# Power.net
KiCad netlist of a schematic drawn in Altium Designer
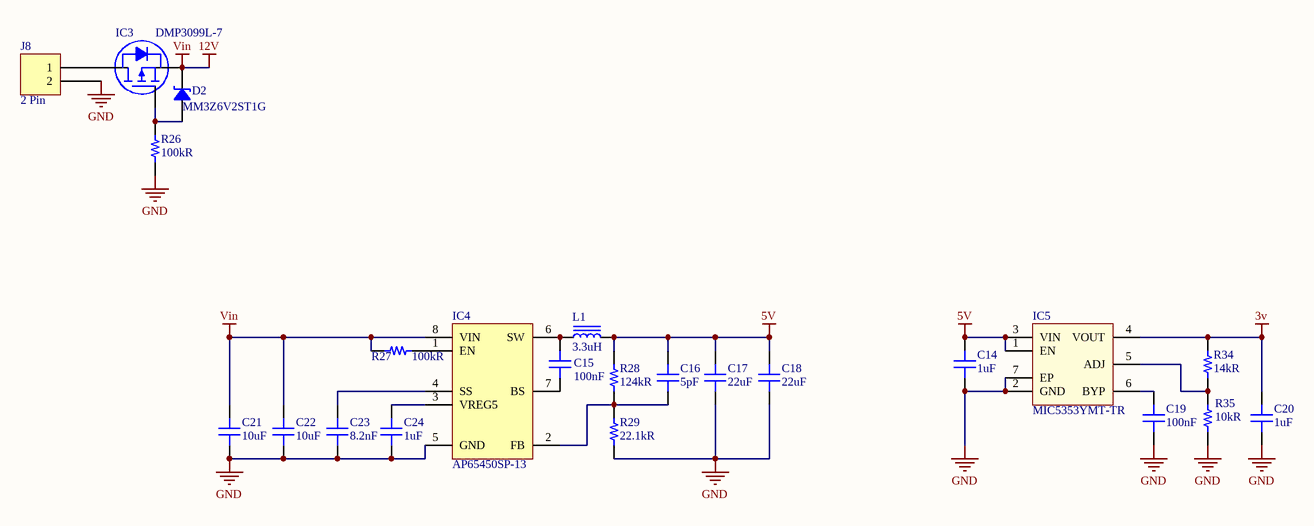
[diagram p0: Power.SchDoc]

(export (version "E")
  (design (tool "Eeschema 10.0.6"))
  (components
    (comp (ref "C14")
      (value "1uF")
      (footprint "CAP 0603/1608")
      (description "Ceramic, SMT Capacitor")
      (fields
        (field (name "MANUFACTURER") "Samsung")
        (field (name "MANUFACTURER PART NUMBER") "CL10A105KP8NNNC")
      )
      (libsource (lib "yildizIoT Library") (part "Capacitor - Ceramic"))
    )
    (comp (ref "C15")
      (value "100nF")
      (footprint "CAP 0603/1608")
      (description "Ceramic, SMT Capacitor")
      (fields
        (field (name "MANUFACTURER") "Samsung")
        (field (name "MANUFACTURER PART NUMBER") "CL10B104JB8NNNC")
      )
      (libsource (lib "yildizIoT Library") (part "Capacitor - Ceramic"))
    )
    (comp (ref "C16")
      (value "5pF")
      (footprint "CAP 0603/1608")
      (description "Ceramic, SMT Capacitor")
      (fields
        (field (name "MANUFACTURER") "Samsung")
        (field (name "MANUFACTURER PART NUMBER") "CL10C050BB8NNNC")
      )
      (libsource (lib "yildizIoT Library") (part "Capacitor - Ceramic"))
    )
    (comp (ref "C17")
      (value "22uF")
      (footprint "CAP 0603/1608")
      (description "Ceramic, SMT Capacitor")
      (fields
        (field (name "MANUFACTURER") "Samsung")
        (field (name "MANUFACTURER PART NUMBER") "CL10A226MPCNUBE")
      )
      (libsource (lib "yildizIoT Library") (part "Capacitor - Ceramic"))
    )
    (comp (ref "C18")
      (value "22uF")
      (footprint "CAP 0603/1608")
      (description "Ceramic, SMT Capacitor")
      (fields
        (field (name "MANUFACTURER") "Samsung")
        (field (name "MANUFACTURER PART NUMBER") "CL10A226MPCNUBE")
      )
      (libsource (lib "yildizIoT Library") (part "Capacitor - Ceramic"))
    )
    (comp (ref "C19")
      (value "100nF")
      (footprint "CAP 0603/1608")
      (description "Ceramic, SMT Capacitor")
      (fields
        (field (name "MANUFACTURER") "Samsung")
        (field (name "MANUFACTURER PART NUMBER") "CL10B104JB8NNNC")
      )
      (libsource (lib "yildizIoT Library") (part "Capacitor - Ceramic"))
    )
    (comp (ref "C20")
      (value "1uF")
      (footprint "CAP 0603/1608")
      (description "Ceramic, SMT Capacitor")
      (fields
        (field (name "MANUFACTURER") "Samsung")
        (field (name "MANUFACTURER PART NUMBER") "CL10A105KP8NNNC")
      )
      (libsource (lib "yildizIoT Library") (part "Capacitor - Ceramic"))
    )
    (comp (ref "C21")
      (value "10uF")
      (footprint "CAP 0603/1608")
      (description "Ceramic, SMT Capacitor")
      (fields
        (field (name "MANUFACTURER") "Samsung")
        (field (name "MANUFACTURER PART NUMBER") "CL10A106MQ8NNNC")
      )
      (libsource (lib "yildizIoT Library") (part "Capacitor - Ceramic"))
    )
    (comp (ref "C22")
      (value "10uF")
      (footprint "CAP 0603/1608")
      (description "Ceramic, SMT Capacitor")
      (fields
        (field (name "MANUFACTURER") "Samsung")
        (field (name "MANUFACTURER PART NUMBER") "CL10A106MQ8NNNC")
      )
      (libsource (lib "yildizIoT Library") (part "Capacitor - Ceramic"))
    )
    (comp (ref "C23")
      (value "8.2nF")
      (footprint "CAP 0603/1608")
      (description "Ceramic, SMT Capacitor")
      (fields
        (field (name "MANUFACTURER") "Walsin Technologies")
        (field (name "MANUFACTURER PART NUMBER") "0603B822K500CT")
      )
      (libsource (lib "yildizIoT Library") (part "Capacitor - Ceramic"))
    )
    (comp (ref "C24")
      (value "1uF")
      (footprint "CAP 0603/1608")
      (description "Ceramic, SMT Capacitor")
      (fields
        (field (name "MANUFACTURER") "Samsung")
        (field (name "MANUFACTURER PART NUMBER") "CL10A105KP8NNNC")
      )
      (libsource (lib "yildizIoT Library") (part "Capacitor - Ceramic"))
    )
    (comp (ref "D2")
      (value "MM3Z6V2ST1G")
      (footprint "SOD323")
      (description "DIODE ZENER 6.2V 300MW SOD323")
      (fields (field (name "MANUFACTURER") "ON Semiconductor") (field (name "TOLERANCE") "2%"))
      (libsource (lib "Celestial Altium Library - altium_library") (part "Diode Zener"))
    )
    (comp (ref "IC3")
      (value "DMP3099L-7")
      (footprint "DIODES SOT-23-3")
      (description "MOSFET P-CH 30V SOT23")
      (fields (field (name "MANUFACTURER") "Diodes"))
      (libsource (lib "Celestial Altium Library - altium_library") (part "DIODES MOSFET P-CH SOT-23-3"))
    )
    (comp (ref "IC4")
      (value "AP65450SP-13")
      (footprint "DIODES SO-8EP")
      (fields (field (name "MANUFACTURER") "Diodes"))
      (libsource (lib "yildizIoT Library") (part "DIODES AP65450"))
    )
    (comp (ref "IC5")
      (value "MIC5353YMT-TR")
      (footprint "MICREL MLF-6 1.6x1.6MM")
      (description "Integrated Circuit")
      (fields (field (name "MANUFACTURER") "Microchip"))
      (libsource (lib "yildizIoT Library") (part "MICROCHIP MIC5353"))
    )
    (comp (ref "J8")
      (value "2 Pin")
      (footprint "TE 282834-2")
      (libsource (lib "yildizIoT Library") (part "2 Pin"))
    )
    (comp (ref "L1")
      (value "3.3uH")
      (footprint "MURATA 1264EY-4R7M=P3")
      (fields
        (field (name "MANUFACTURER") "Murata")
        (field (name "MANUFACTURER PART NUMBER") "1264EY-3R3N=P3")
        (field (name "TOLERANCE") "30%")
      )
      (libsource (lib "yildizIoT Library") (part "Inductor Iron Core"))
    )
    (comp (ref "R26")
      (value "100kR")
      (footprint "RES 0603/1608")
      (description "Ceramic, SMT Capacitor")
      (fields
        (field (name "MANUFACTURER") "Susumu")
        (field (name "MANUFACTURER PART NUMBER") "RR0816P-104-D")
      )
      (libsource (lib "yildizIoT Library") (part "Resistor_Chip"))
    )
    (comp (ref "R27")
      (value "100kR")
      (footprint "RES 0603/1608")
      (description "Ceramic, SMT Capacitor")
      (fields
        (field (name "MANUFACTURER") "Susumu")
        (field (name "MANUFACTURER PART NUMBER") "RR0816P-104-D")
      )
      (libsource (lib "yildizIoT Library") (part "Resistor_Chip"))
    )
    (comp (ref "R28")
      (value "124kR")
      (footprint "RES 0603/1608")
      (description "Ceramic, SMT Capacitor")
      (fields
        (field (name "MANUFACTURER") "Stackpole Electronics")
        (field (name "MANUFACTURER PART NUMBER") "RMCF0603FT124K")
      )
      (libsource (lib "yildizIoT Library") (part "Resistor_Chip"))
    )
    (comp (ref "R29")
      (value "22.1kR")
      (footprint "RES 0603/1608")
      (description "Ceramic, SMT Capacitor")
      (fields
        (field (name "MANUFACTURER") "Stackpole Electronics")
        (field (name "MANUFACTURER PART NUMBER") "RMCF0603FT22K1")
      )
      (libsource (lib "yildizIoT Library") (part "Resistor_Chip"))
    )
    (comp (ref "R34")
      (value "14kR")
      (footprint "RES 0603/1608")
      (description "Ceramic, SMT Capacitor")
      (fields
        (field (name "MANUFACTURER") "Yageo")
        (field (name "MANUFACTURER PART NUMBER") "RC0603FR-0714KL")
      )
      (libsource (lib "yildizIoT Library") (part "Resistor_Chip"))
    )
    (comp (ref "R35")
      (value "10kR")
      (footprint "RES 0603/1608")
      (description "Ceramic, SMT Capacitor")
      (fields
        (field (name "MANUFACTURER") "Stackpole Electronics")
        (field (name "MANUFACTURER PART NUMBER") "RNCP0603FTD10K0")
      )
      (libsource (lib "yildizIoT Library") (part "Resistor_Chip"))
    )
  )
  (nets
    (net (code "1") (name "3v") (class "Default")
      (node (ref "C20") (pin "2") (pinfunction "2_2") (pintype "passive"))
      (node (ref "IC5") (pin "4") (pinfunction "VOUT_4") (pintype "passive"))
      (node (ref "R34") (pin "2") (pinfunction "2_2") (pintype "passive"))
    )
    (net (code "2") (name "5V") (class "Default")
      (node (ref "C14") (pin "2") (pinfunction "2_2") (pintype "passive"))
      (node (ref "C16") (pin "2") (pinfunction "2_2") (pintype "passive"))
      (node (ref "C17") (pin "2") (pinfunction "2_2") (pintype "passive"))
      (node (ref "C18") (pin "2") (pinfunction "2_2") (pintype "passive"))
      (node (ref "IC5") (pin "1") (pinfunction "EN_1") (pintype "passive"))
      (node (ref "IC5") (pin "3") (pinfunction "VIN_3") (pintype "passive"))
      (node (ref "L1") (pin "2") (pinfunction "2_2") (pintype "passive"))
      (node (ref "R28") (pin "1") (pinfunction "1_1") (pintype "passive"))
    )
    (net (code "3") (name "12V") (class "Default")
      (node (ref "C21") (pin "2") (pinfunction "2_2") (pintype "passive"))
      (node (ref "C22") (pin "2") (pinfunction "2_2") (pintype "passive"))
      (node (ref "D2") (pin "2") (pinfunction "2_2") (pintype "passive"))
      (node (ref "IC3") (pin "2") (pinfunction "S_2") (pintype "passive"))
      (node (ref "IC4") (pin "8") (pinfunction "VIN_8") (pintype "power_in"))
      (node (ref "R27") (pin "1") (pinfunction "1_1") (pintype "passive"))
    )
    (net (code "4") (name "GND") (class "Default")
      (node (ref "C14") (pin "1") (pinfunction "1_1") (pintype "passive"))
      (node (ref "C17") (pin "1") (pinfunction "1_1") (pintype "passive"))
      (node (ref "C18") (pin "1") (pinfunction "1_1") (pintype "passive"))
      (node (ref "C19") (pin "1") (pinfunction "1_1") (pintype "passive"))
      (node (ref "C20") (pin "1") (pinfunction "1_1") (pintype "passive"))
      (node (ref "C21") (pin "1") (pinfunction "1_1") (pintype "passive"))
      (node (ref "C22") (pin "1") (pinfunction "1_1") (pintype "passive"))
      (node (ref "C23") (pin "1") (pinfunction "1_1") (pintype "passive"))
      (node (ref "C24") (pin "1") (pinfunction "1_1") (pintype "passive"))
      (node (ref "IC4") (pin "5") (pinfunction "GND_5") (pintype "power_in"))
      (node (ref "IC5") (pin "2") (pinfunction "GND_2") (pintype "passive"))
      (node (ref "IC5") (pin "7") (pinfunction "EP_7") (pintype "power_in"))
      (node (ref "J8") (pin "2") (pinfunction "2_2") (pintype "passive"))
      (node (ref "R26") (pin "1") (pinfunction "1_1") (pintype "passive"))
      (node (ref "R29") (pin "2") (pinfunction "2_2") (pintype "passive"))
      (node (ref "R35") (pin "2") (pinfunction "2_2") (pintype "passive"))
    )
    (net (code "5") (name "Net-(IC3-D)") (class "Default")
      (node (ref "IC3") (pin "3") (pinfunction "D_3") (pintype "passive"))
      (node (ref "J8") (pin "1") (pinfunction "1_1") (pintype "passive"))
    )
    (net (code "6") (name "Net-(IC3-G)") (class "Default")
      (node (ref "D2") (pin "1") (pinfunction "1_1") (pintype "passive"))
      (node (ref "IC3") (pin "1") (pinfunction "G_1") (pintype "passive"))
      (node (ref "R26") (pin "2") (pinfunction "2_2") (pintype "passive"))
    )
    (net (code "7") (name "Net-(IC4-BS)") (class "Default")
      (node (ref "C15") (pin "2") (pinfunction "2_2") (pintype "passive"))
      (node (ref "IC4") (pin "7") (pinfunction "BS_7") (pintype "power_in"))
    )
    (net (code "8") (name "Net-(IC4-EN)") (class "Default")
      (node (ref "IC4") (pin "1") (pinfunction "EN_1") (pintype "power_in"))
      (node (ref "R27") (pin "2") (pinfunction "2_2") (pintype "passive"))
    )
    (net (code "9") (name "Net-(IC4-FB)") (class "Default")
      (node (ref "C16") (pin "1") (pinfunction "1_1") (pintype "passive"))
      (node (ref "IC4") (pin "2") (pinfunction "FB_2") (pintype "power_in"))
      (node (ref "R28") (pin "2") (pinfunction "2_2") (pintype "passive"))
      (node (ref "R29") (pin "1") (pinfunction "1_1") (pintype "passive"))
    )
    (net (code "10") (name "Net-(IC4-SS)") (class "Default")
      (node (ref "C23") (pin "2") (pinfunction "2_2") (pintype "passive"))
      (node (ref "IC4") (pin "4") (pinfunction "SS_4") (pintype "power_in"))
    )
    (net (code "11") (name "Net-(IC4-SW)") (class "Default")
      (node (ref "C15") (pin "1") (pinfunction "1_1") (pintype "passive"))
      (node (ref "IC4") (pin "6") (pinfunction "SW_6") (pintype "power_in"))
      (node (ref "L1") (pin "1") (pinfunction "1_1") (pintype "passive"))
    )
    (net (code "12") (name "Net-(IC4-VREG5)") (class "Default")
      (node (ref "C24") (pin "2") (pinfunction "2_2") (pintype "passive"))
      (node (ref "IC4") (pin "3") (pinfunction "VREG5_3") (pintype "power_in"))
    )
    (net (code "13") (name "Net-(IC5-ADJ)") (class "Default")
      (node (ref "IC5") (pin "5") (pinfunction "ADJ_5") (pintype "passive"))
      (node (ref "R34") (pin "1") (pinfunction "1_1") (pintype "passive"))
      (node (ref "R35") (pin "1") (pinfunction "1_1") (pintype "passive"))
    )
    (net (code "14") (name "Net-(IC5-BYP)") (class "Default")
      (node (ref "C19") (pin "2") (pinfunction "2_2") (pintype "passive"))
      (node (ref "IC5") (pin "6") (pinfunction "BYP_6") (pintype "passive"))
    )
  )
)
